# ADC_DECOUPLING.net
KiCad netlist of a schematic drawn in Altium Designer
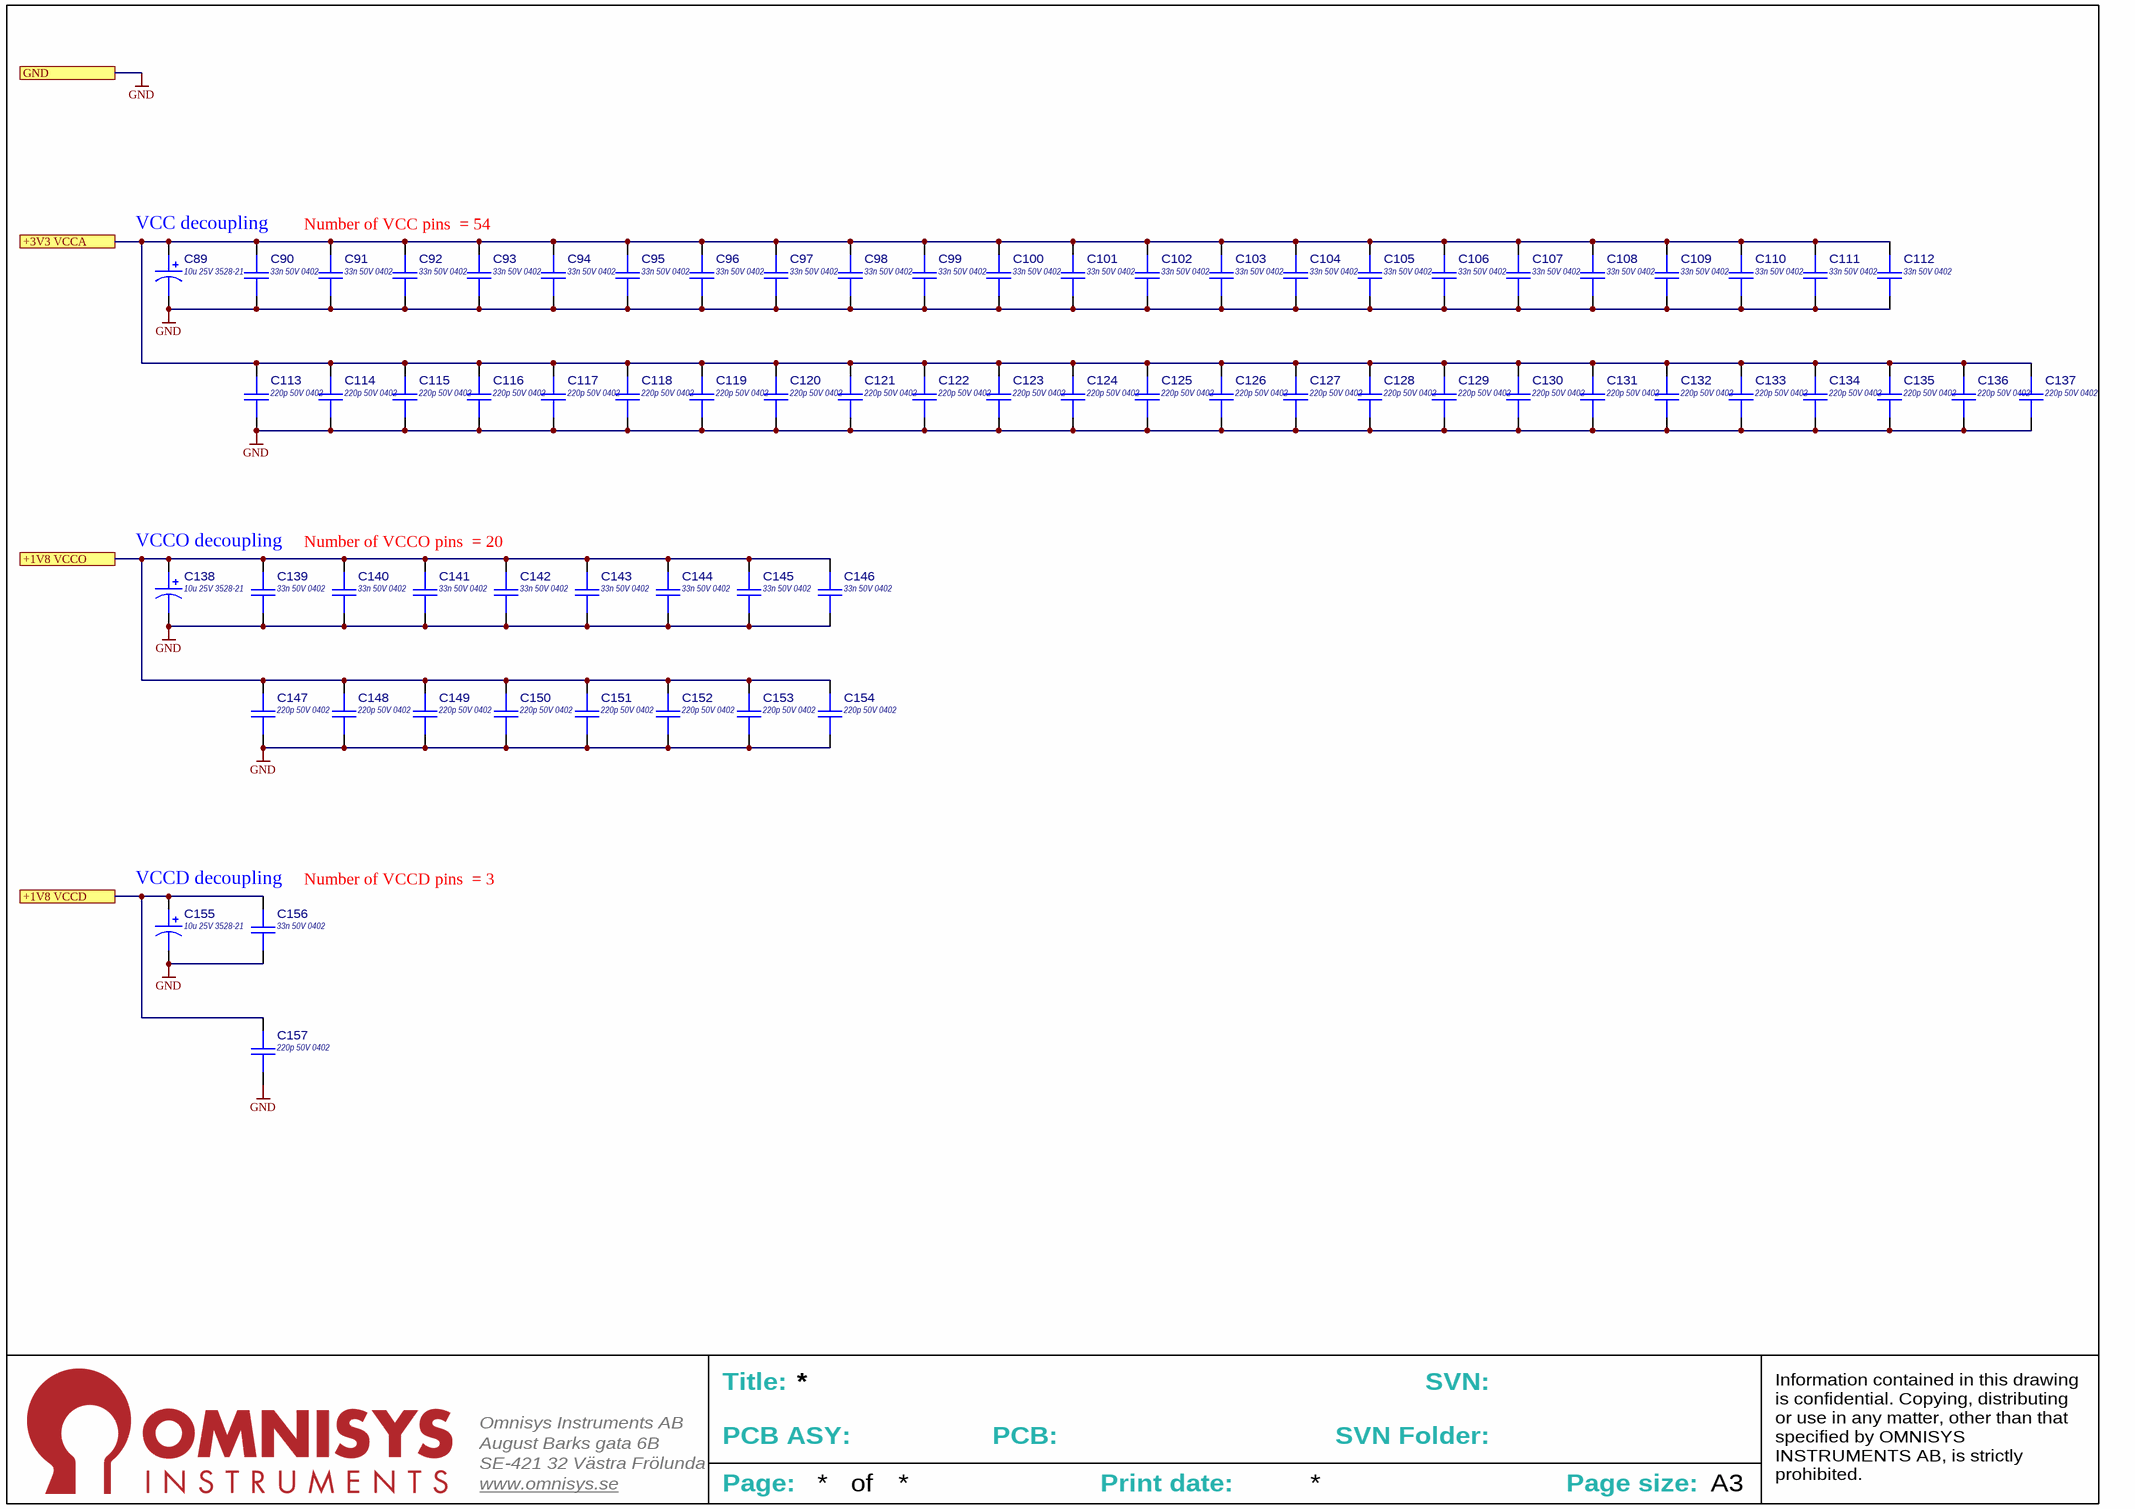
[diagram p0: ADC_DECOUPLING.SchDoc]

(export (version "E")
  (design (tool "Eeschema 10.0.6"))
  (components
    (comp (ref "C89")
      (value "10u 25V 3528-21")
      (footprint "CAPMP3528X21N")
      (description "Standard tantalum capacitor, 10u 25V 3528-21, Case B, TAJB106M025RNJ")
      (fields (field (name "TOLERANCE") "±20%") (field (name "PARTNUMBER") "TAJB106M025RNJ"))
      (libsource (lib "Omnisys Vault") (part "CAP-2PIN-POL"))
    )
    (comp (ref "C90")
      (value "33n 50V 0402")
      (footprint "CAPC1005X55L")
      (description "33n 50V X7R ±10% 0402 (1005 metric)")
      (fields (field (name "PARTNUMBER") "GRM155R71H333KE14") (field (name "TOLERANCE") "10%"))
      (libsource (lib "Omnisys Vault") (part "CAP-2PIN"))
    )
    (comp (ref "C91")
      (value "33n 50V 0402")
      (footprint "CAPC1005X55L")
      (description "33n 50V X7R ±10% 0402 (1005 metric)")
      (fields (field (name "PARTNUMBER") "GRM155R71H333KE14") (field (name "TOLERANCE") "10%"))
      (libsource (lib "Omnisys Vault") (part "CAP-2PIN"))
    )
    (comp (ref "C92")
      (value "33n 50V 0402")
      (footprint "CAPC1005X55L")
      (description "33n 50V X7R ±10% 0402 (1005 metric)")
      (fields (field (name "PARTNUMBER") "GRM155R71H333KE14") (field (name "TOLERANCE") "10%"))
      (libsource (lib "Omnisys Vault") (part "CAP-2PIN"))
    )
    (comp (ref "C93")
      (value "33n 50V 0402")
      (footprint "CAPC1005X55L")
      (description "33n 50V X7R ±10% 0402 (1005 metric)")
      (fields (field (name "PARTNUMBER") "GRM155R71H333KE14") (field (name "TOLERANCE") "10%"))
      (libsource (lib "Omnisys Vault") (part "CAP-2PIN"))
    )
    (comp (ref "C94")
      (value "33n 50V 0402")
      (footprint "CAPC1005X55L")
      (description "33n 50V X7R ±10% 0402 (1005 metric)")
      (fields (field (name "PARTNUMBER") "GRM155R71H333KE14") (field (name "TOLERANCE") "10%"))
      (libsource (lib "Omnisys Vault") (part "CAP-2PIN"))
    )
    (comp (ref "C95")
      (value "33n 50V 0402")
      (footprint "CAPC1005X55L")
      (description "33n 50V X7R ±10% 0402 (1005 metric)")
      (fields (field (name "PARTNUMBER") "GRM155R71H333KE14") (field (name "TOLERANCE") "10%"))
      (libsource (lib "Omnisys Vault") (part "CAP-2PIN"))
    )
    (comp (ref "C96")
      (value "33n 50V 0402")
      (footprint "CAPC1005X55L")
      (description "33n 50V X7R ±10% 0402 (1005 metric)")
      (fields (field (name "PARTNUMBER") "GRM155R71H333KE14") (field (name "TOLERANCE") "10%"))
      (libsource (lib "Omnisys Vault") (part "CAP-2PIN"))
    )
    (comp (ref "C97")
      (value "33n 50V 0402")
      (footprint "CAPC1005X55L")
      (description "33n 50V X7R ±10% 0402 (1005 metric)")
      (fields (field (name "PARTNUMBER") "GRM155R71H333KE14") (field (name "TOLERANCE") "10%"))
      (libsource (lib "Omnisys Vault") (part "CAP-2PIN"))
    )
    (comp (ref "C98")
      (value "33n 50V 0402")
      (footprint "CAPC1005X55L")
      (description "33n 50V X7R ±10% 0402 (1005 metric)")
      (fields (field (name "PARTNUMBER") "GRM155R71H333KE14") (field (name "TOLERANCE") "10%"))
      (libsource (lib "Omnisys Vault") (part "CAP-2PIN"))
    )
    (comp (ref "C99")
      (value "33n 50V 0402")
      (footprint "CAPC1005X55L")
      (description "33n 50V X7R ±10% 0402 (1005 metric)")
      (fields (field (name "PARTNUMBER") "GRM155R71H333KE14") (field (name "TOLERANCE") "10%"))
      (libsource (lib "Omnisys Vault") (part "CAP-2PIN"))
    )
    (comp (ref "C100")
      (value "33n 50V 0402")
      (footprint "CAPC1005X55L")
      (description "33n 50V X7R ±10% 0402 (1005 metric)")
      (fields (field (name "PARTNUMBER") "GRM155R71H333KE14") (field (name "TOLERANCE") "10%"))
      (libsource (lib "Omnisys Vault") (part "CAP-2PIN"))
    )
    (comp (ref "C101")
      (value "33n 50V 0402")
      (footprint "CAPC1005X55L")
      (description "33n 50V X7R ±10% 0402 (1005 metric)")
      (fields (field (name "PARTNUMBER") "GRM155R71H333KE14") (field (name "TOLERANCE") "10%"))
      (libsource (lib "Omnisys Vault") (part "CAP-2PIN"))
    )
    (comp (ref "C102")
      (value "33n 50V 0402")
      (footprint "CAPC1005X55L")
      (description "33n 50V X7R ±10% 0402 (1005 metric)")
      (fields (field (name "PARTNUMBER") "GRM155R71H333KE14") (field (name "TOLERANCE") "10%"))
      (libsource (lib "Omnisys Vault") (part "CAP-2PIN"))
    )
    (comp (ref "C103")
      (value "33n 50V 0402")
      (footprint "CAPC1005X55L")
      (description "33n 50V X7R ±10% 0402 (1005 metric)")
      (fields (field (name "PARTNUMBER") "GRM155R71H333KE14") (field (name "TOLERANCE") "10%"))
      (libsource (lib "Omnisys Vault") (part "CAP-2PIN"))
    )
    (comp (ref "C104")
      (value "33n 50V 0402")
      (footprint "CAPC1005X55L")
      (description "33n 50V X7R ±10% 0402 (1005 metric)")
      (fields (field (name "PARTNUMBER") "GRM155R71H333KE14") (field (name "TOLERANCE") "10%"))
      (libsource (lib "Omnisys Vault") (part "CAP-2PIN"))
    )
    (comp (ref "C105")
      (value "33n 50V 0402")
      (footprint "CAPC1005X55L")
      (description "33n 50V X7R ±10% 0402 (1005 metric)")
      (fields (field (name "PARTNUMBER") "GRM155R71H333KE14") (field (name "TOLERANCE") "10%"))
      (libsource (lib "Omnisys Vault") (part "CAP-2PIN"))
    )
    (comp (ref "C106")
      (value "33n 50V 0402")
      (footprint "CAPC1005X55L")
      (description "33n 50V X7R ±10% 0402 (1005 metric)")
      (fields (field (name "PARTNUMBER") "GRM155R71H333KE14") (field (name "TOLERANCE") "10%"))
      (libsource (lib "Omnisys Vault") (part "CAP-2PIN"))
    )
    (comp (ref "C107")
      (value "33n 50V 0402")
      (footprint "CAPC1005X55L")
      (description "33n 50V X7R ±10% 0402 (1005 metric)")
      (fields (field (name "PARTNUMBER") "GRM155R71H333KE14") (field (name "TOLERANCE") "10%"))
      (libsource (lib "Omnisys Vault") (part "CAP-2PIN"))
    )
    (comp (ref "C108")
      (value "33n 50V 0402")
      (footprint "CAPC1005X55L")
      (description "33n 50V X7R ±10% 0402 (1005 metric)")
      (fields (field (name "PARTNUMBER") "GRM155R71H333KE14") (field (name "TOLERANCE") "10%"))
      (libsource (lib "Omnisys Vault") (part "CAP-2PIN"))
    )
    (comp (ref "C109")
      (value "33n 50V 0402")
      (footprint "CAPC1005X55L")
      (description "33n 50V X7R ±10% 0402 (1005 metric)")
      (fields (field (name "PARTNUMBER") "GRM155R71H333KE14") (field (name "TOLERANCE") "10%"))
      (libsource (lib "Omnisys Vault") (part "CAP-2PIN"))
    )
    (comp (ref "C110")
      (value "33n 50V 0402")
      (footprint "CAPC1005X55L")
      (description "33n 50V X7R ±10% 0402 (1005 metric)")
      (fields (field (name "PARTNUMBER") "GRM155R71H333KE14") (field (name "TOLERANCE") "10%"))
      (libsource (lib "Omnisys Vault") (part "CAP-2PIN"))
    )
    (comp (ref "C111")
      (value "33n 50V 0402")
      (footprint "CAPC1005X55L")
      (description "33n 50V X7R ±10% 0402 (1005 metric)")
      (fields (field (name "PARTNUMBER") "GRM155R71H333KE14") (field (name "TOLERANCE") "10%"))
      (libsource (lib "Omnisys Vault") (part "CAP-2PIN"))
    )
    (comp (ref "C112")
      (value "33n 50V 0402")
      (footprint "CAPC1005X55L")
      (description "33n 50V X7R ±10% 0402 (1005 metric)")
      (fields (field (name "PARTNUMBER") "GRM155R71H333KE14") (field (name "TOLERANCE") "10%"))
      (libsource (lib "Omnisys Vault") (part "CAP-2PIN"))
    )
    (comp (ref "C113")
      (value "220p 50V 0402")
      (footprint "CAPC1005X55L")
      (description "220p 50V X7R ±10% 0402 (1005 metric)")
      (fields (field (name "PARTNUMBER") "GRM155R71H221KA01") (field (name "TOLERANCE") "10%"))
      (libsource (lib "Omnisys Vault") (part "CAP-2PIN"))
    )
    (comp (ref "C114")
      (value "220p 50V 0402")
      (footprint "CAPC1005X55L")
      (description "220p 50V X7R ±10% 0402 (1005 metric)")
      (fields (field (name "PARTNUMBER") "GRM155R71H221KA01") (field (name "TOLERANCE") "10%"))
      (libsource (lib "Omnisys Vault") (part "CAP-2PIN"))
    )
    (comp (ref "C115")
      (value "220p 50V 0402")
      (footprint "CAPC1005X55L")
      (description "220p 50V X7R ±10% 0402 (1005 metric)")
      (fields (field (name "PARTNUMBER") "GRM155R71H221KA01") (field (name "TOLERANCE") "10%"))
      (libsource (lib "Omnisys Vault") (part "CAP-2PIN"))
    )
    (comp (ref "C116")
      (value "220p 50V 0402")
      (footprint "CAPC1005X55L")
      (description "220p 50V X7R ±10% 0402 (1005 metric)")
      (fields (field (name "PARTNUMBER") "GRM155R71H221KA01") (field (name "TOLERANCE") "10%"))
      (libsource (lib "Omnisys Vault") (part "CAP-2PIN"))
    )
    (comp (ref "C117")
      (value "220p 50V 0402")
      (footprint "CAPC1005X55L")
      (description "220p 50V X7R ±10% 0402 (1005 metric)")
      (fields (field (name "PARTNUMBER") "GRM155R71H221KA01") (field (name "TOLERANCE") "10%"))
      (libsource (lib "Omnisys Vault") (part "CAP-2PIN"))
    )
    (comp (ref "C118")
      (value "220p 50V 0402")
      (footprint "CAPC1005X55L")
      (description "220p 50V X7R ±10% 0402 (1005 metric)")
      (fields (field (name "PARTNUMBER") "GRM155R71H221KA01") (field (name "TOLERANCE") "10%"))
      (libsource (lib "Omnisys Vault") (part "CAP-2PIN"))
    )
    (comp (ref "C119")
      (value "220p 50V 0402")
      (footprint "CAPC1005X55L")
      (description "220p 50V X7R ±10% 0402 (1005 metric)")
      (fields (field (name "PARTNUMBER") "GRM155R71H221KA01") (field (name "TOLERANCE") "10%"))
      (libsource (lib "Omnisys Vault") (part "CAP-2PIN"))
    )
    (comp (ref "C120")
      (value "220p 50V 0402")
      (footprint "CAPC1005X55L")
      (description "220p 50V X7R ±10% 0402 (1005 metric)")
      (fields (field (name "PARTNUMBER") "GRM155R71H221KA01") (field (name "TOLERANCE") "10%"))
      (libsource (lib "Omnisys Vault") (part "CAP-2PIN"))
    )
    (comp (ref "C121")
      (value "220p 50V 0402")
      (footprint "CAPC1005X55L")
      (description "220p 50V X7R ±10% 0402 (1005 metric)")
      (fields (field (name "PARTNUMBER") "GRM155R71H221KA01") (field (name "TOLERANCE") "10%"))
      (libsource (lib "Omnisys Vault") (part "CAP-2PIN"))
    )
    (comp (ref "C122")
      (value "220p 50V 0402")
      (footprint "CAPC1005X55L")
      (description "220p 50V X7R ±10% 0402 (1005 metric)")
      (fields (field (name "PARTNUMBER") "GRM155R71H221KA01") (field (name "TOLERANCE") "10%"))
      (libsource (lib "Omnisys Vault") (part "CAP-2PIN"))
    )
    (comp (ref "C123")
      (value "220p 50V 0402")
      (footprint "CAPC1005X55L")
      (description "220p 50V X7R ±10% 0402 (1005 metric)")
      (fields (field (name "PARTNUMBER") "GRM155R71H221KA01") (field (name "TOLERANCE") "10%"))
      (libsource (lib "Omnisys Vault") (part "CAP-2PIN"))
    )
    (comp (ref "C124")
      (value "220p 50V 0402")
      (footprint "CAPC1005X55L")
      (description "220p 50V X7R ±10% 0402 (1005 metric)")
      (fields (field (name "PARTNUMBER") "GRM155R71H221KA01") (field (name "TOLERANCE") "10%"))
      (libsource (lib "Omnisys Vault") (part "CAP-2PIN"))
    )
    (comp (ref "C125")
      (value "220p 50V 0402")
      (footprint "CAPC1005X55L")
      (description "220p 50V X7R ±10% 0402 (1005 metric)")
      (fields (field (name "PARTNUMBER") "GRM155R71H221KA01") (field (name "TOLERANCE") "10%"))
      (libsource (lib "Omnisys Vault") (part "CAP-2PIN"))
    )
    (comp (ref "C126")
      (value "220p 50V 0402")
      (footprint "CAPC1005X55L")
      (description "220p 50V X7R ±10% 0402 (1005 metric)")
      (fields (field (name "PARTNUMBER") "GRM155R71H221KA01") (field (name "TOLERANCE") "10%"))
      (libsource (lib "Omnisys Vault") (part "CAP-2PIN"))
    )
    (comp (ref "C127")
      (value "220p 50V 0402")
      (footprint "CAPC1005X55L")
      (description "220p 50V X7R ±10% 0402 (1005 metric)")
      (fields (field (name "PARTNUMBER") "GRM155R71H221KA01") (field (name "TOLERANCE") "10%"))
      (libsource (lib "Omnisys Vault") (part "CAP-2PIN"))
    )
    (comp (ref "C128")
      (value "220p 50V 0402")
      (footprint "CAPC1005X55L")
      (description "220p 50V X7R ±10% 0402 (1005 metric)")
      (fields (field (name "PARTNUMBER") "GRM155R71H221KA01") (field (name "TOLERANCE") "10%"))
      (libsource (lib "Omnisys Vault") (part "CAP-2PIN"))
    )
    (comp (ref "C129")
      (value "220p 50V 0402")
      (footprint "CAPC1005X55L")
      (description "220p 50V X7R ±10% 0402 (1005 metric)")
      (fields (field (name "PARTNUMBER") "GRM155R71H221KA01") (field (name "TOLERANCE") "10%"))
      (libsource (lib "Omnisys Vault") (part "CAP-2PIN"))
    )
    (comp (ref "C130")
      (value "220p 50V 0402")
      (footprint "CAPC1005X55L")
      (description "220p 50V X7R ±10% 0402 (1005 metric)")
      (fields (field (name "PARTNUMBER") "GRM155R71H221KA01") (field (name "TOLERANCE") "10%"))
      (libsource (lib "Omnisys Vault") (part "CAP-2PIN"))
    )
    (comp (ref "C131")
      (value "220p 50V 0402")
      (footprint "CAPC1005X55L")
      (description "220p 50V X7R ±10% 0402 (1005 metric)")
      (fields (field (name "PARTNUMBER") "GRM155R71H221KA01") (field (name "TOLERANCE") "10%"))
      (libsource (lib "Omnisys Vault") (part "CAP-2PIN"))
    )
    (comp (ref "C132")
      (value "220p 50V 0402")
      (footprint "CAPC1005X55L")
      (description "220p 50V X7R ±10% 0402 (1005 metric)")
      (fields (field (name "PARTNUMBER") "GRM155R71H221KA01") (field (name "TOLERANCE") "10%"))
      (libsource (lib "Omnisys Vault") (part "CAP-2PIN"))
    )
    (comp (ref "C133")
      (value "220p 50V 0402")
      (footprint "CAPC1005X55L")
      (description "220p 50V X7R ±10% 0402 (1005 metric)")
      (fields (field (name "PARTNUMBER") "GRM155R71H221KA01") (field (name "TOLERANCE") "10%"))
      (libsource (lib "Omnisys Vault") (part "CAP-2PIN"))
    )
    (comp (ref "C134")
      (value "220p 50V 0402")
      (footprint "CAPC1005X55L")
      (description "220p 50V X7R ±10% 0402 (1005 metric)")
      (fields (field (name "PARTNUMBER") "GRM155R71H221KA01") (field (name "TOLERANCE") "10%"))
      (libsource (lib "Omnisys Vault") (part "CAP-2PIN"))
    )
    (comp (ref "C135")
      (value "220p 50V 0402")
      (footprint "CAPC1005X55L")
      (description "220p 50V X7R ±10% 0402 (1005 metric)")
      (fields (field (name "PARTNUMBER") "GRM155R71H221KA01") (field (name "TOLERANCE") "10%"))
      (libsource (lib "Omnisys Vault") (part "CAP-2PIN"))
    )
    (comp (ref "C136")
      (value "220p 50V 0402")
      (footprint "CAPC1005X55L")
      (description "220p 50V X7R ±10% 0402 (1005 metric)")
      (fields (field (name "PARTNUMBER") "GRM155R71H221KA01") (field (name "TOLERANCE") "10%"))
      (libsource (lib "Omnisys Vault") (part "CAP-2PIN"))
    )
    (comp (ref "C137")
      (value "220p 50V 0402")
      (footprint "CAPC1005X55L")
      (description "220p 50V X7R ±10% 0402 (1005 metric)")
      (fields (field (name "PARTNUMBER") "GRM155R71H221KA01") (field (name "TOLERANCE") "10%"))
      (libsource (lib "Omnisys Vault") (part "CAP-2PIN"))
    )
    (comp (ref "C138")
      (value "10u 25V 3528-21")
      (footprint "CAPMP3528X21N")
      (description "Standard tantalum capacitor, 10u 25V 3528-21, Case B, TAJB106M025RNJ")
      (fields (field (name "TOLERANCE") "±20%") (field (name "PARTNUMBER") "TAJB106M025RNJ"))
      (libsource (lib "Omnisys Vault") (part "CAP-2PIN-POL"))
    )
    (comp (ref "C139")
      (value "33n 50V 0402")
      (footprint "CAPC1005X55N")
      (description "33n 50V X7R ±10% 0402 (1005 metric)")
      (fields (field (name "PARTNUMBER") "GRM155R71H333KE14") (field (name "TOLERANCE") "10%"))
      (libsource (lib "Omnisys Vault") (part "CAP-2PIN"))
    )
    (comp (ref "C140")
      (value "33n 50V 0402")
      (footprint "CAPC1005X55N")
      (description "33n 50V X7R ±10% 0402 (1005 metric)")
      (fields (field (name "PARTNUMBER") "GRM155R71H333KE14") (field (name "TOLERANCE") "10%"))
      (libsource (lib "Omnisys Vault") (part "CAP-2PIN"))
    )
    (comp (ref "C141")
      (value "33n 50V 0402")
      (footprint "CAPC1005X55N")
      (description "33n 50V X7R ±10% 0402 (1005 metric)")
      (fields (field (name "PARTNUMBER") "GRM155R71H333KE14") (field (name "TOLERANCE") "10%"))
      (libsource (lib "Omnisys Vault") (part "CAP-2PIN"))
    )
    (comp (ref "C142")
      (value "33n 50V 0402")
      (footprint "CAPC1005X55N")
      (description "33n 50V X7R ±10% 0402 (1005 metric)")
      (fields (field (name "PARTNUMBER") "GRM155R71H333KE14") (field (name "TOLERANCE") "10%"))
      (libsource (lib "Omnisys Vault") (part "CAP-2PIN"))
    )
    (comp (ref "C143")
      (value "33n 50V 0402")
      (footprint "CAPC1005X55N")
      (description "33n 50V X7R ±10% 0402 (1005 metric)")
      (fields (field (name "PARTNUMBER") "GRM155R71H333KE14") (field (name "TOLERANCE") "10%"))
      (libsource (lib "Omnisys Vault") (part "CAP-2PIN"))
    )
    (comp (ref "C144")
      (value "33n 50V 0402")
      (footprint "CAPC1005X55N")
      (description "33n 50V X7R ±10% 0402 (1005 metric)")
      (fields (field (name "PARTNUMBER") "GRM155R71H333KE14") (field (name "TOLERANCE") "10%"))
      (libsource (lib "Omnisys Vault") (part "CAP-2PIN"))
    )
    (comp (ref "C145")
      (value "33n 50V 0402")
      (footprint "CAPC1005X55N")
      (description "33n 50V X7R ±10% 0402 (1005 metric)")
      (fields (field (name "PARTNUMBER") "GRM155R71H333KE14") (field (name "TOLERANCE") "10%"))
      (libsource (lib "Omnisys Vault") (part "CAP-2PIN"))
    )
    (comp (ref "C146")
      (value "33n 50V 0402")
      (footprint "CAPC1005X55N")
      (description "33n 50V X7R ±10% 0402 (1005 metric)")
      (fields (field (name "PARTNUMBER") "GRM155R71H333KE14") (field (name "TOLERANCE") "10%"))
      (libsource (lib "Omnisys Vault") (part "CAP-2PIN"))
    )
    (comp (ref "C147")
      (value "220p 50V 0402")
      (footprint "CAPC1005X55N")
      (description "220p 50V X7R ±10% 0402 (1005 metric)")
      (fields (field (name "PARTNUMBER") "GRM155R71H221KA01") (field (name "TOLERANCE") "10%"))
      (libsource (lib "Omnisys Vault") (part "CAP-2PIN"))
    )
    (comp (ref "C148")
      (value "220p 50V 0402")
      (footprint "CAPC1005X55N")
      (description "220p 50V X7R ±10% 0402 (1005 metric)")
      (fields (field (name "PARTNUMBER") "GRM155R71H221KA01") (field (name "TOLERANCE") "10%"))
      (libsource (lib "Omnisys Vault") (part "CAP-2PIN"))
    )
    (comp (ref "C149")
      (value "220p 50V 0402")
      (footprint "CAPC1005X55N")
      (description "220p 50V X7R ±10% 0402 (1005 metric)")
      (fields (field (name "PARTNUMBER") "GRM155R71H221KA01") (field (name "TOLERANCE") "10%"))
      (libsource (lib "Omnisys Vault") (part "CAP-2PIN"))
    )
    (comp (ref "C150")
      (value "220p 50V 0402")
      (footprint "CAPC1005X55N")
      (description "220p 50V X7R ±10% 0402 (1005 metric)")
      (fields (field (name "PARTNUMBER") "GRM155R71H221KA01") (field (name "TOLERANCE") "10%"))
      (libsource (lib "Omnisys Vault") (part "CAP-2PIN"))
    )
    (comp (ref "C151")
      (value "220p 50V 0402")
      (footprint "CAPC1005X55N")
      (description "220p 50V X7R ±10% 0402 (1005 metric)")
      (fields (field (name "PARTNUMBER") "GRM155R71H221KA01") (field (name "TOLERANCE") "10%"))
      (libsource (lib "Omnisys Vault") (part "CAP-2PIN"))
    )
    (comp (ref "C152")
      (value "220p 50V 0402")
      (footprint "CAPC1005X55N")
      (description "220p 50V X7R ±10% 0402 (1005 metric)")
      (fields (field (name "PARTNUMBER") "GRM155R71H221KA01") (field (name "TOLERANCE") "10%"))
      (libsource (lib "Omnisys Vault") (part "CAP-2PIN"))
    )
    (comp (ref "C153")
      (value "220p 50V 0402")
      (footprint "CAPC1005X55N")
      (description "220p 50V X7R ±10% 0402 (1005 metric)")
      (fields (field (name "PARTNUMBER") "GRM155R71H221KA01") (field (name "TOLERANCE") "10%"))
      (libsource (lib "Omnisys Vault") (part "CAP-2PIN"))
    )
    (comp (ref "C154")
      (value "220p 50V 0402")
      (footprint "CAPC1005X55N")
      (description "220p 50V X7R ±10% 0402 (1005 metric)")
      (fields (field (name "PARTNUMBER") "GRM155R71H221KA01") (field (name "TOLERANCE") "10%"))
      (libsource (lib "Omnisys Vault") (part "CAP-2PIN"))
    )
    (comp (ref "C155")
      (value "10u 25V 3528-21")
      (footprint "CAPMP3528X21N")
      (description "Standard tantalum capacitor, 10u 25V 3528-21, Case B, TAJB106M025RNJ")
      (fields (field (name "TOLERANCE") "±20%") (field (name "PARTNUMBER") "TAJB106M025RNJ"))
      (libsource (lib "Omnisys Vault") (part "CAP-2PIN-POL"))
    )
    (comp (ref "C156")
      (value "33n 50V 0402")
      (footprint "CAPC1005X55N")
      (description "33n 50V X7R ±10% 0402 (1005 metric)")
      (fields (field (name "PARTNUMBER") "GRM155R71H333KE14") (field (name "TOLERANCE") "10%"))
      (libsource (lib "Omnisys Vault") (part "CAP-2PIN"))
    )
    (comp (ref "C157")
      (value "220p 50V 0402")
      (footprint "CAPC1005X55N")
      (description "220p 50V X7R ±10% 0402 (1005 metric)")
      (fields (field (name "PARTNUMBER") "GRM155R71H221KA01") (field (name "TOLERANCE") "10%"))
      (libsource (lib "Omnisys Vault") (part "CAP-2PIN"))
    )
  )
  (nets
    (net (code "1") (name "/+1V8 VCCD") (class "Default")
      (node (ref "C155") (pin "1") (pinfunction "1_1") (pintype "passive"))
      (node (ref "C156") (pin "2") (pinfunction "2_2") (pintype "passive"))
      (node (ref "C157") (pin "2") (pinfunction "2_2") (pintype "passive"))
    )
    (net (code "2") (name "/+1V8 VCCO") (class "Default")
      (node (ref "C138") (pin "1") (pinfunction "1_1") (pintype "passive"))
      (node (ref "C139") (pin "2") (pinfunction "2_2") (pintype "passive"))
      (node (ref "C140") (pin "2") (pinfunction "2_2") (pintype "passive"))
      (node (ref "C141") (pin "2") (pinfunction "2_2") (pintype "passive"))
      (node (ref "C142") (pin "2") (pinfunction "2_2") (pintype "passive"))
      (node (ref "C143") (pin "2") (pinfunction "2_2") (pintype "passive"))
      (node (ref "C144") (pin "2") (pinfunction "2_2") (pintype "passive"))
      (node (ref "C145") (pin "2") (pinfunction "2_2") (pintype "passive"))
      (node (ref "C146") (pin "2") (pinfunction "2_2") (pintype "passive"))
      (node (ref "C147") (pin "2") (pinfunction "2_2") (pintype "passive"))
      (node (ref "C148") (pin "2") (pinfunction "2_2") (pintype "passive"))
      (node (ref "C149") (pin "2") (pinfunction "2_2") (pintype "passive"))
      (node (ref "C150") (pin "2") (pinfunction "2_2") (pintype "passive"))
      (node (ref "C151") (pin "2") (pinfunction "2_2") (pintype "passive"))
      (node (ref "C152") (pin "2") (pinfunction "2_2") (pintype "passive"))
      (node (ref "C153") (pin "2") (pinfunction "2_2") (pintype "passive"))
      (node (ref "C154") (pin "2") (pinfunction "2_2") (pintype "passive"))
    )
    (net (code "3") (name "/+3V3 VCCA") (class "Default")
      (node (ref "C100") (pin "2") (pinfunction "2_2") (pintype "passive"))
      (node (ref "C101") (pin "2") (pinfunction "2_2") (pintype "passive"))
      (node (ref "C102") (pin "2") (pinfunction "2_2") (pintype "passive"))
      (node (ref "C103") (pin "2") (pinfunction "2_2") (pintype "passive"))
      (node (ref "C104") (pin "2") (pinfunction "2_2") (pintype "passive"))
      (node (ref "C105") (pin "2") (pinfunction "2_2") (pintype "passive"))
      (node (ref "C106") (pin "2") (pinfunction "2_2") (pintype "passive"))
      (node (ref "C107") (pin "2") (pinfunction "2_2") (pintype "passive"))
      (node (ref "C108") (pin "2") (pinfunction "2_2") (pintype "passive"))
      (node (ref "C109") (pin "2") (pinfunction "2_2") (pintype "passive"))
      (node (ref "C110") (pin "2") (pinfunction "2_2") (pintype "passive"))
      (node (ref "C111") (pin "2") (pinfunction "2_2") (pintype "passive"))
      (node (ref "C112") (pin "2") (pinfunction "2_2") (pintype "passive"))
      (node (ref "C113") (pin "2") (pinfunction "2_2") (pintype "passive"))
      (node (ref "C114") (pin "2") (pinfunction "2_2") (pintype "passive"))
      (node (ref "C115") (pin "2") (pinfunction "2_2") (pintype "passive"))
      (node (ref "C116") (pin "2") (pinfunction "2_2") (pintype "passive"))
      (node (ref "C117") (pin "2") (pinfunction "2_2") (pintype "passive"))
      (node (ref "C118") (pin "2") (pinfunction "2_2") (pintype "passive"))
      (node (ref "C119") (pin "2") (pinfunction "2_2") (pintype "passive"))
      (node (ref "C120") (pin "2") (pinfunction "2_2") (pintype "passive"))
      (node (ref "C121") (pin "2") (pinfunction "2_2") (pintype "passive"))
      (node (ref "C122") (pin "2") (pinfunction "2_2") (pintype "passive"))
      (node (ref "C123") (pin "2") (pinfunction "2_2") (pintype "passive"))
      (node (ref "C124") (pin "2") (pinfunction "2_2") (pintype "passive"))
      (node (ref "C125") (pin "2") (pinfunction "2_2") (pintype "passive"))
      (node (ref "C126") (pin "2") (pinfunction "2_2") (pintype "passive"))
      (node (ref "C127") (pin "2") (pinfunction "2_2") (pintype "passive"))
      (node (ref "C128") (pin "2") (pinfunction "2_2") (pintype "passive"))
      (node (ref "C129") (pin "2") (pinfunction "2_2") (pintype "passive"))
      (node (ref "C130") (pin "2") (pinfunction "2_2") (pintype "passive"))
      (node (ref "C131") (pin "2") (pinfunction "2_2") (pintype "passive"))
      (node (ref "C132") (pin "2") (pinfunction "2_2") (pintype "passive"))
      (node (ref "C133") (pin "2") (pinfunction "2_2") (pintype "passive"))
      (node (ref "C134") (pin "2") (pinfunction "2_2") (pintype "passive"))
      (node (ref "C135") (pin "2") (pinfunction "2_2") (pintype "passive"))
      (node (ref "C136") (pin "2") (pinfunction "2_2") (pintype "passive"))
      (node (ref "C137") (pin "2") (pinfunction "2_2") (pintype "passive"))
      (node (ref "C89") (pin "1") (pinfunction "1_1") (pintype "passive"))
      (node (ref "C90") (pin "2") (pinfunction "2_2") (pintype "passive"))
      (node (ref "C91") (pin "2") (pinfunction "2_2") (pintype "passive"))
      (node (ref "C92") (pin "2") (pinfunction "2_2") (pintype "passive"))
      (node (ref "C93") (pin "2") (pinfunction "2_2") (pintype "passive"))
      (node (ref "C94") (pin "2") (pinfunction "2_2") (pintype "passive"))
      (node (ref "C95") (pin "2") (pinfunction "2_2") (pintype "passive"))
      (node (ref "C96") (pin "2") (pinfunction "2_2") (pintype "passive"))
      (node (ref "C97") (pin "2") (pinfunction "2_2") (pintype "passive"))
      (node (ref "C98") (pin "2") (pinfunction "2_2") (pintype "passive"))
      (node (ref "C99") (pin "2") (pinfunction "2_2") (pintype "passive"))
    )
    (net (code "4") (name "GND") (class "Default")
      (node (ref "C100") (pin "1") (pinfunction "1_1") (pintype "passive"))
      (node (ref "C101") (pin "1") (pinfunction "1_1") (pintype "passive"))
      (node (ref "C102") (pin "1") (pinfunction "1_1") (pintype "passive"))
      (node (ref "C103") (pin "1") (pinfunction "1_1") (pintype "passive"))
      (node (ref "C104") (pin "1") (pinfunction "1_1") (pintype "passive"))
      (node (ref "C105") (pin "1") (pinfunction "1_1") (pintype "passive"))
      (node (ref "C106") (pin "1") (pinfunction "1_1") (pintype "passive"))
      (node (ref "C107") (pin "1") (pinfunction "1_1") (pintype "passive"))
      (node (ref "C108") (pin "1") (pinfunction "1_1") (pintype "passive"))
      (node (ref "C109") (pin "1") (pinfunction "1_1") (pintype "passive"))
      (node (ref "C110") (pin "1") (pinfunction "1_1") (pintype "passive"))
      (node (ref "C111") (pin "1") (pinfunction "1_1") (pintype "passive"))
      (node (ref "C112") (pin "1") (pinfunction "1_1") (pintype "passive"))
      (node (ref "C113") (pin "1") (pinfunction "1_1") (pintype "passive"))
      (node (ref "C114") (pin "1") (pinfunction "1_1") (pintype "passive"))
      (node (ref "C115") (pin "1") (pinfunction "1_1") (pintype "passive"))
      (node (ref "C116") (pin "1") (pinfunction "1_1") (pintype "passive"))
      (node (ref "C117") (pin "1") (pinfunction "1_1") (pintype "passive"))
      (node (ref "C118") (pin "1") (pinfunction "1_1") (pintype "passive"))
      (node (ref "C119") (pin "1") (pinfunction "1_1") (pintype "passive"))
      (node (ref "C120") (pin "1") (pinfunction "1_1") (pintype "passive"))
      (node (ref "C121") (pin "1") (pinfunction "1_1") (pintype "passive"))
      (node (ref "C122") (pin "1") (pinfunction "1_1") (pintype "passive"))
      (node (ref "C123") (pin "1") (pinfunction "1_1") (pintype "passive"))
      (node (ref "C124") (pin "1") (pinfunction "1_1") (pintype "passive"))
      (node (ref "C125") (pin "1") (pinfunction "1_1") (pintype "passive"))
      (node (ref "C126") (pin "1") (pinfunction "1_1") (pintype "passive"))
      (node (ref "C127") (pin "1") (pinfunction "1_1") (pintype "passive"))
      (node (ref "C128") (pin "1") (pinfunction "1_1") (pintype "passive"))
      (node (ref "C129") (pin "1") (pinfunction "1_1") (pintype "passive"))
      (node (ref "C130") (pin "1") (pinfunction "1_1") (pintype "passive"))
      (node (ref "C131") (pin "1") (pinfunction "1_1") (pintype "passive"))
      (node (ref "C132") (pin "1") (pinfunction "1_1") (pintype "passive"))
      (node (ref "C133") (pin "1") (pinfunction "1_1") (pintype "passive"))
      (node (ref "C134") (pin "1") (pinfunction "1_1") (pintype "passive"))
      (node (ref "C135") (pin "1") (pinfunction "1_1") (pintype "passive"))
      (node (ref "C136") (pin "1") (pinfunction "1_1") (pintype "passive"))
      (node (ref "C137") (pin "1") (pinfunction "1_1") (pintype "passive"))
      (node (ref "C138") (pin "2") (pinfunction "2_2") (pintype "passive"))
      (node (ref "C139") (pin "1") (pinfunction "1_1") (pintype "passive"))
      (node (ref "C140") (pin "1") (pinfunction "1_1") (pintype "passive"))
      (node (ref "C141") (pin "1") (pinfunction "1_1") (pintype "passive"))
      (node (ref "C142") (pin "1") (pinfunction "1_1") (pintype "passive"))
      (node (ref "C143") (pin "1") (pinfunction "1_1") (pintype "passive"))
      (node (ref "C144") (pin "1") (pinfunction "1_1") (pintype "passive"))
      (node (ref "C145") (pin "1") (pinfunction "1_1") (pintype "passive"))
      (node (ref "C146") (pin "1") (pinfunction "1_1") (pintype "passive"))
      (node (ref "C147") (pin "1") (pinfunction "1_1") (pintype "passive"))
      (node (ref "C148") (pin "1") (pinfunction "1_1") (pintype "passive"))
      (node (ref "C149") (pin "1") (pinfunction "1_1") (pintype "passive"))
      (node (ref "C150") (pin "1") (pinfunction "1_1") (pintype "passive"))
      (node (ref "C151") (pin "1") (pinfunction "1_1") (pintype "passive"))
      (node (ref "C152") (pin "1") (pinfunction "1_1") (pintype "passive"))
      (node (ref "C153") (pin "1") (pinfunction "1_1") (pintype "passive"))
      (node (ref "C154") (pin "1") (pinfunction "1_1") (pintype "passive"))
      (node (ref "C155") (pin "2") (pinfunction "2_2") (pintype "passive"))
      (node (ref "C156") (pin "1") (pinfunction "1_1") (pintype "passive"))
      (node (ref "C157") (pin "1") (pinfunction "1_1") (pintype "passive"))
      (node (ref "C89") (pin "2") (pinfunction "2_2") (pintype "passive"))
      (node (ref "C90") (pin "1") (pinfunction "1_1") (pintype "passive"))
      (node (ref "C91") (pin "1") (pinfunction "1_1") (pintype "passive"))
      (node (ref "C92") (pin "1") (pinfunction "1_1") (pintype "passive"))
      (node (ref "C93") (pin "1") (pinfunction "1_1") (pintype "passive"))
      (node (ref "C94") (pin "1") (pinfunction "1_1") (pintype "passive"))
      (node (ref "C95") (pin "1") (pinfunction "1_1") (pintype "passive"))
      (node (ref "C96") (pin "1") (pinfunction "1_1") (pintype "passive"))
      (node (ref "C97") (pin "1") (pinfunction "1_1") (pintype "passive"))
      (node (ref "C98") (pin "1") (pinfunction "1_1") (pintype "passive"))
      (node (ref "C99") (pin "1") (pinfunction "1_1") (pintype "passive"))
    )
  )
)
